# design.net
KiCad netlist of a schematic drawn in EasyEDA Pro
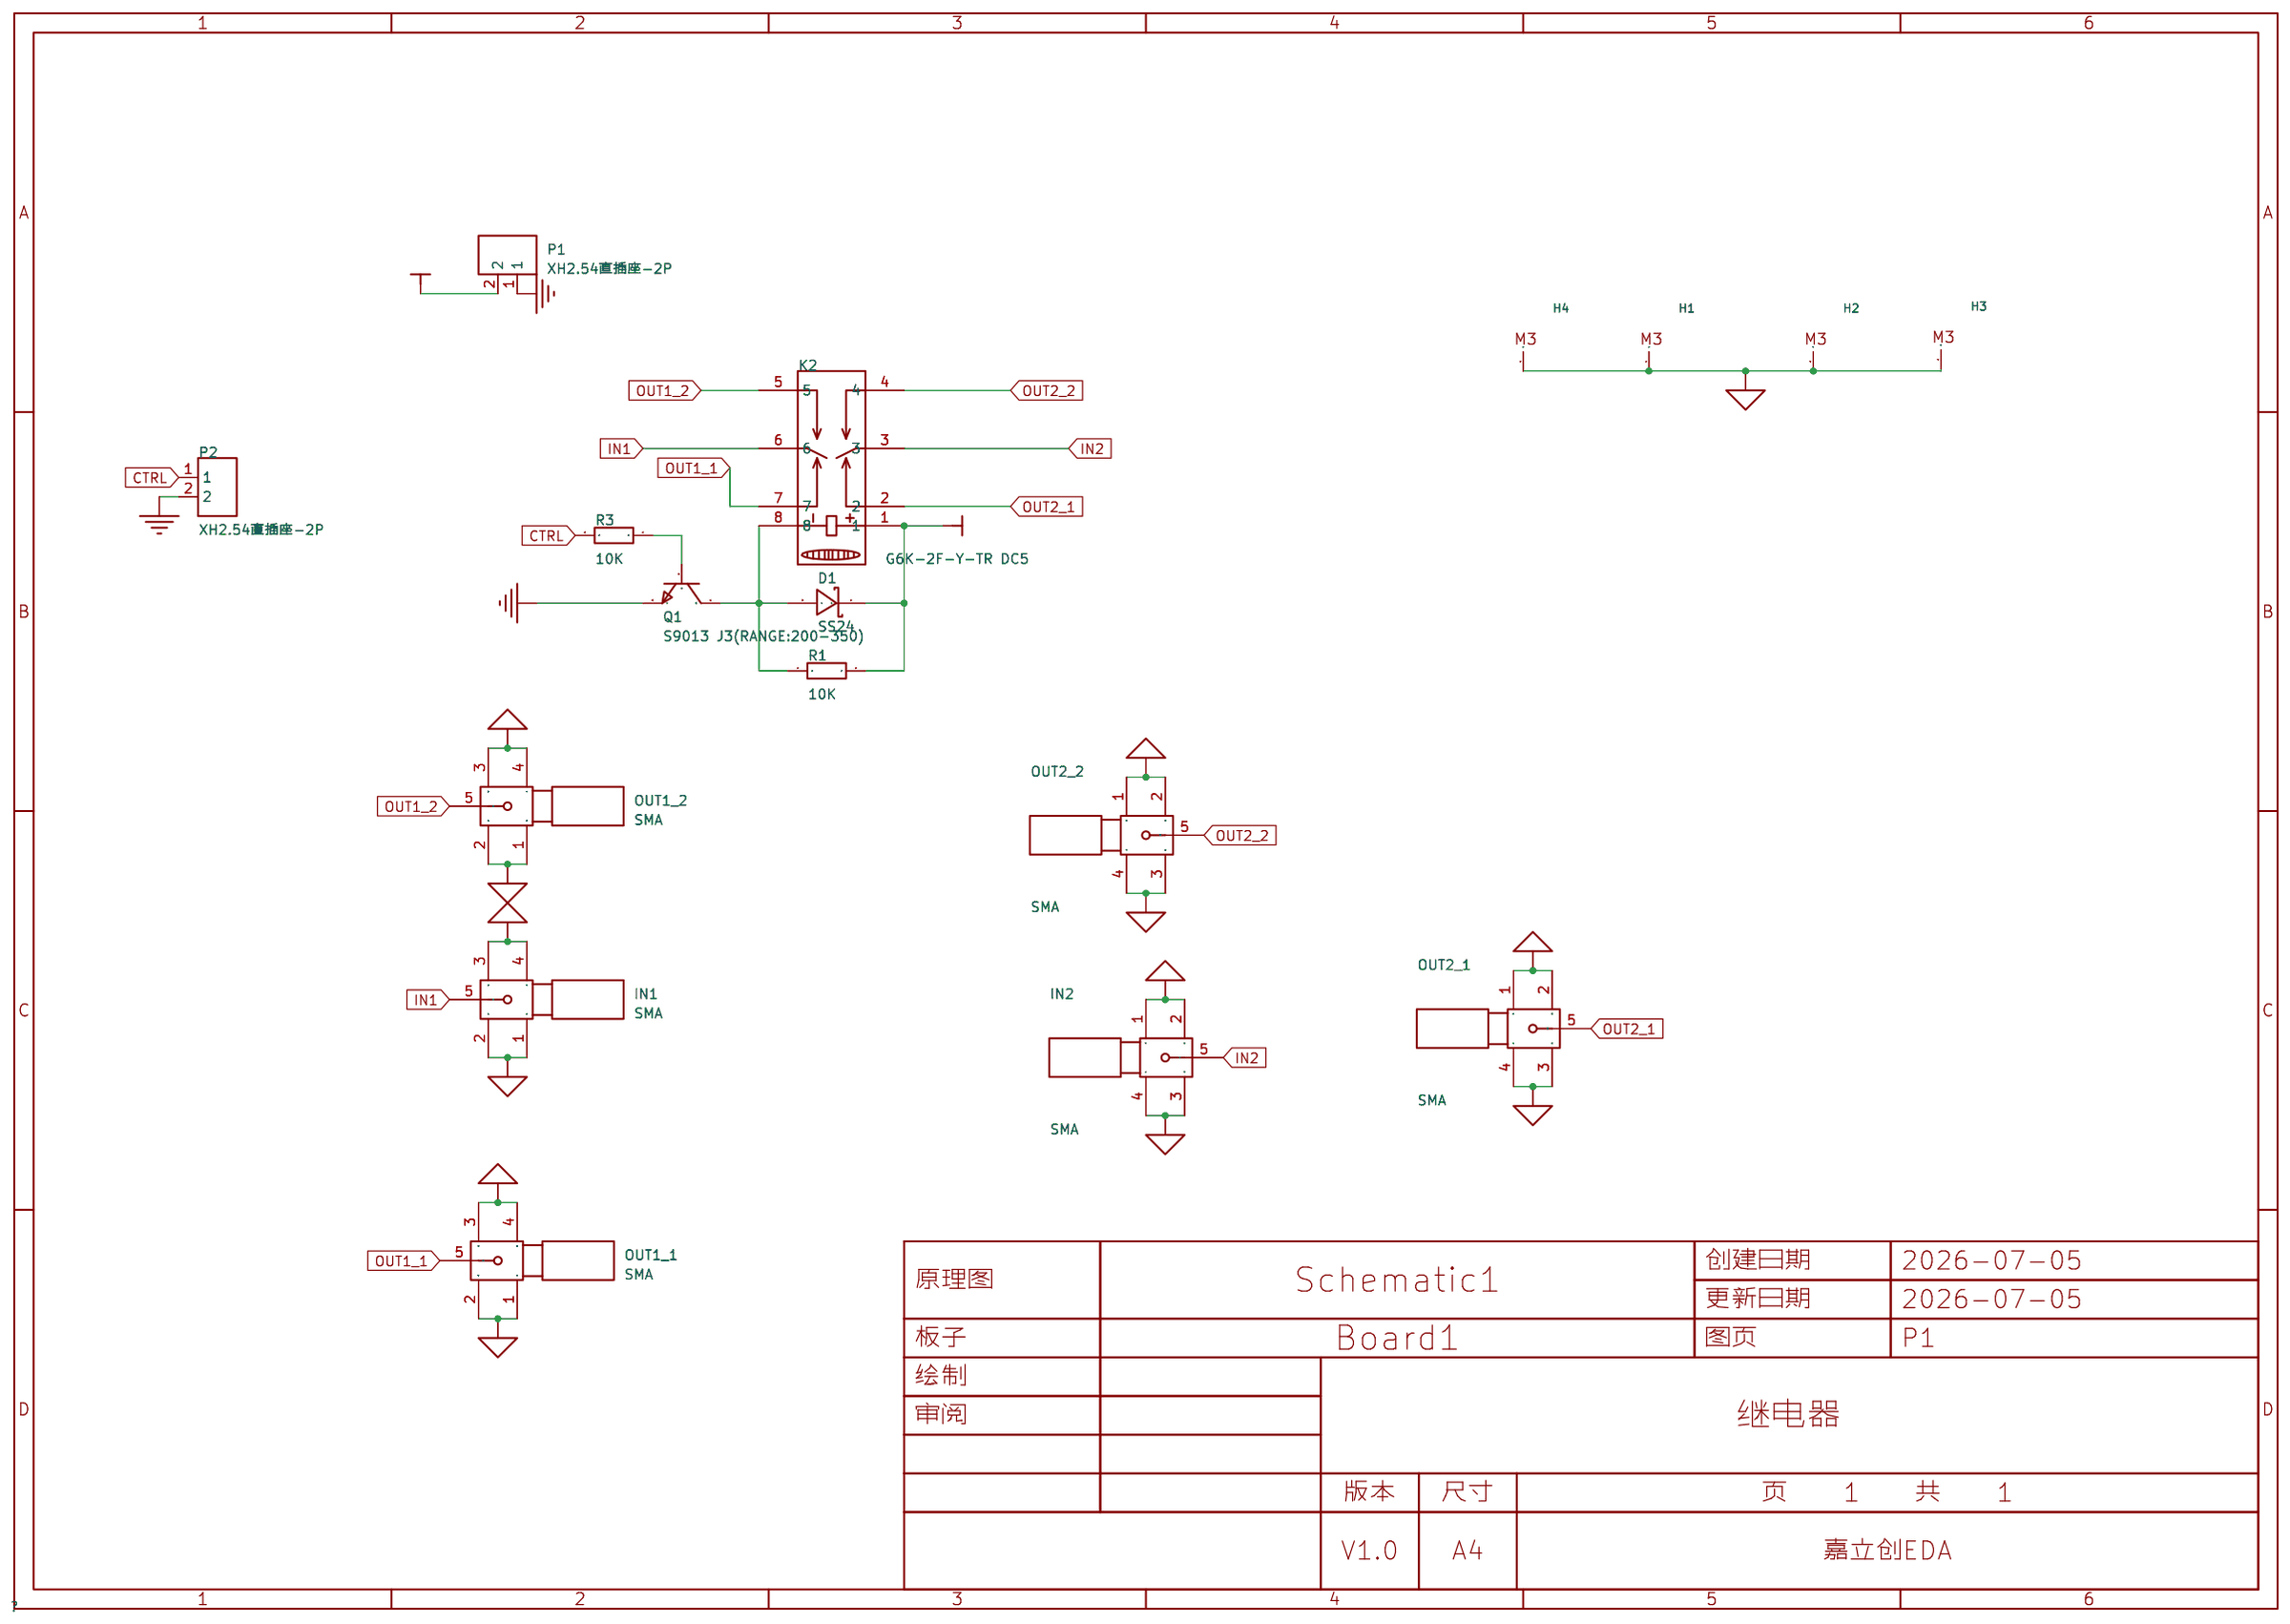
[diagram p0: schematic sheet]

(export (version "E")
  (design (tool "Eeschema 10.0.6"))
  (components
    (comp (ref "D1")
      (value "SS24")
      (footprint "easyedapro:SMA_L4.3-W2.6-LS5.2-RD")
      (libsource (lib "easyedapro") (part "SS24_C13444"))
    )
    (comp (ref "H1") (value "~") (footprint "easyedapro:M3") (libsource (lib "easyedapro") (part "螺丝孔")))
    (comp (ref "H2") (value "~") (footprint "easyedapro:M3") (libsource (lib "easyedapro") (part "螺丝孔")))
    (comp (ref "H3") (value "~") (footprint "easyedapro:M3") (libsource (lib "easyedapro") (part "螺丝孔")))
    (comp (ref "H4") (value "~") (footprint "easyedapro:M3") (libsource (lib "easyedapro") (part "螺丝孔")))
    (comp (ref "IN1")
      (value "SMA")
      (footprint "easyedapro:SMA-SMD_BWSMA-KE-P001")
      (libsource (lib "easyedapro") (part "SMA_C9900018296"))
    )
    (comp (ref "IN2")
      (value "SMA")
      (footprint "easyedapro:SMA-SMD_BWSMA-KE-P001")
      (libsource (lib "easyedapro") (part "SMA_C9900018296"))
    )
    (comp (ref "K2")
      (value "G6K-2F-Y-TR DC5")
      (footprint "easyedapro:RELAY-SMD_G6K-2F-X-XX")
      (description "线圈电压:5V;触点形式:两组转换:2C(双刀双掷-转换);触点容量(电阻负载):-;最大切换电压:125V@AC；60V@DC;最大切换电流:1A;")
      (fields (field (name "Manufacturer") "OMRON(欧姆龙)"))
      (libsource (lib "easyedapro") (part "G6K-2F-Y-DC5"))
    )
    (comp (ref "OUT1_1")
      (value "SMA")
      (footprint "easyedapro:SMA-SMD_BWSMA-KE-P001")
      (libsource (lib "easyedapro") (part "SMA_C9900018296"))
    )
    (comp (ref "OUT1_2")
      (value "SMA")
      (footprint "easyedapro:SMA-SMD_BWSMA-KE-P001")
      (libsource (lib "easyedapro") (part "SMA_C9900018296"))
    )
    (comp (ref "OUT2_1")
      (value "SMA")
      (footprint "easyedapro:SMA-SMD_BWSMA-KE-P001")
      (libsource (lib "easyedapro") (part "SMA_C9900018296"))
    )
    (comp (ref "OUT2_2")
      (value "SMA")
      (footprint "easyedapro:SMA-SMD_BWSMA-KE-P001")
      (libsource (lib "easyedapro") (part "SMA_C9900018296"))
    )
    (comp (ref "P1")
      (value "XH2.54直插座-2P")
      (footprint "easyedapro:CONN-TH_XH2.54-2P")
      (libsource (lib "easyedapro") (part "XH2.54直插座-2P"))
    )
    (comp (ref "P2")
      (value "XH2.54直插座-2P")
      (footprint "easyedapro:CONN-TH_XH2.54-2P")
      (libsource (lib "easyedapro") (part "XH2.54直插座-2P"))
    )
    (comp (ref "Q1")
      (value "S9013 J3(RANGE:200-350)")
      (footprint "easyedapro:SOT-23-3_L2.9-W1.3-P1.90-LS2.4-BR")
      (fields (field (name "Manufacturer") "CJ(江苏长电/长晶)"))
      (libsource (lib "easyedapro") (part "S9013 J3"))
    )
    (comp (ref "R1") (value "10K") (footprint "easyedapro:R0805") (libsource (lib "easyedapro") (part "电阻")))
    (comp (ref "R3") (value "10K") (footprint "easyedapro:R0805") (libsource (lib "easyedapro") (part "电阻")))
  )
  (nets
    (net (code "1") (name "AGND") (class "Default")
      (node (ref "H1") (pin "1") (pinfunction "1_1") (pintype "input"))
      (node (ref "H2") (pin "1") (pinfunction "1_1") (pintype "input"))
      (node (ref "H3") (pin "1") (pinfunction "1_1") (pintype "input"))
      (node (ref "H4") (pin "1") (pinfunction "1_1") (pintype "input"))
      (node (ref "IN1") (pin "1") (pinfunction "1_1") (pintype "unspecified"))
      (node (ref "IN1") (pin "2") (pinfunction "2_2") (pintype "unspecified"))
      (node (ref "IN1") (pin "3") (pinfunction "3_3") (pintype "unspecified"))
      (node (ref "IN1") (pin "4") (pinfunction "4_4") (pintype "unspecified"))
      (node (ref "IN2") (pin "1") (pinfunction "1_1") (pintype "unspecified"))
      (node (ref "IN2") (pin "2") (pinfunction "2_2") (pintype "unspecified"))
      (node (ref "IN2") (pin "3") (pinfunction "3_3") (pintype "unspecified"))
      (node (ref "IN2") (pin "4") (pinfunction "4_4") (pintype "unspecified"))
      (node (ref "OUT1_1") (pin "1") (pinfunction "1_1") (pintype "unspecified"))
      (node (ref "OUT1_1") (pin "2") (pinfunction "2_2") (pintype "unspecified"))
      (node (ref "OUT1_1") (pin "3") (pinfunction "3_3") (pintype "unspecified"))
      (node (ref "OUT1_1") (pin "4") (pinfunction "4_4") (pintype "unspecified"))
      (node (ref "OUT1_2") (pin "1") (pinfunction "1_1") (pintype "unspecified"))
      (node (ref "OUT1_2") (pin "2") (pinfunction "2_2") (pintype "unspecified"))
      (node (ref "OUT1_2") (pin "3") (pinfunction "3_3") (pintype "unspecified"))
      (node (ref "OUT1_2") (pin "4") (pinfunction "4_4") (pintype "unspecified"))
      (node (ref "OUT2_1") (pin "1") (pinfunction "1_1") (pintype "unspecified"))
      (node (ref "OUT2_1") (pin "2") (pinfunction "2_2") (pintype "unspecified"))
      (node (ref "OUT2_1") (pin "3") (pinfunction "3_3") (pintype "unspecified"))
      (node (ref "OUT2_1") (pin "4") (pinfunction "4_4") (pintype "unspecified"))
      (node (ref "OUT2_2") (pin "1") (pinfunction "1_1") (pintype "unspecified"))
      (node (ref "OUT2_2") (pin "2") (pinfunction "2_2") (pintype "unspecified"))
      (node (ref "OUT2_2") (pin "3") (pinfunction "3_3") (pintype "unspecified"))
      (node (ref "OUT2_2") (pin "4") (pinfunction "4_4") (pintype "unspecified"))
    )
    (net (code "2") (name "CTRL") (class "Default")
      (node (ref "P2") (pin "1") (pinfunction "1_1") (pintype "unspecified"))
      (node (ref "R3") (pin "2") (pinfunction "2_2") (pintype "input"))
    )
    (net (code "3") (name "GND") (class "Default")
      (node (ref "P1") (pin "1") (pinfunction "1_1") (pintype "unspecified"))
      (node (ref "P2") (pin "2") (pinfunction "2_2") (pintype "unspecified"))
      (node (ref "Q1") (pin "2") (pinfunction "E_2") (pintype "unspecified"))
    )
    (net (code "4") (name "IN1") (class "Default")
      (node (ref "IN1") (pin "5") (pinfunction "5_5") (pintype "unspecified"))
      (node (ref "K2") (pin "6") (pinfunction "6_6") (pintype "unspecified"))
    )
    (net (code "5") (name "IN2") (class "Default")
      (node (ref "IN2") (pin "5") (pinfunction "5_5") (pintype "unspecified"))
      (node (ref "K2") (pin "3") (pinfunction "3_3") (pintype "unspecified"))
    )
    (net (code "6") (name "Net-(D1-A)") (class "Default")
      (node (ref "D1") (pin "2") (pinfunction "A_2") (pintype "unspecified"))
      (node (ref "K2") (pin "8") (pinfunction "8_8") (pintype "unspecified"))
      (node (ref "Q1") (pin "3") (pinfunction "C_3") (pintype "unspecified"))
      (node (ref "R1") (pin "1") (pinfunction "1_1") (pintype "input"))
    )
    (net (code "7") (name "Net-(Q1-B)") (class "Default")
      (node (ref "Q1") (pin "1") (pinfunction "B_1") (pintype "unspecified"))
      (node (ref "R3") (pin "1") (pinfunction "1_1") (pintype "input"))
    )
    (net (code "8") (name "OUT1_1") (class "Default")
      (node (ref "K2") (pin "7") (pinfunction "7_7") (pintype "unspecified"))
      (node (ref "OUT1_1") (pin "5") (pinfunction "5_5") (pintype "unspecified"))
    )
    (net (code "9") (name "OUT1_2") (class "Default")
      (node (ref "K2") (pin "5") (pinfunction "5_5") (pintype "unspecified"))
      (node (ref "OUT1_2") (pin "5") (pinfunction "5_5") (pintype "unspecified"))
    )
    (net (code "10") (name "OUT2_1") (class "Default")
      (node (ref "K2") (pin "2") (pinfunction "2_2") (pintype "unspecified"))
      (node (ref "OUT2_1") (pin "5") (pinfunction "5_5") (pintype "unspecified"))
    )
    (net (code "11") (name "OUT2_2") (class "Default")
      (node (ref "K2") (pin "4") (pinfunction "4_4") (pintype "unspecified"))
      (node (ref "OUT2_2") (pin "5") (pinfunction "5_5") (pintype "unspecified"))
    )
    (net (code "12") (name "VCC") (class "Default")
      (node (ref "D1") (pin "1") (pinfunction "K_1") (pintype "unspecified"))
      (node (ref "K2") (pin "1") (pinfunction "1_1") (pintype "unspecified"))
      (node (ref "P1") (pin "2") (pinfunction "2_2") (pintype "unspecified"))
      (node (ref "R1") (pin "2") (pinfunction "2_2") (pintype "input"))
    )
  )
)
